# keyboard-tester.net
KiCad netlist of a schematic drawn in EAGLE
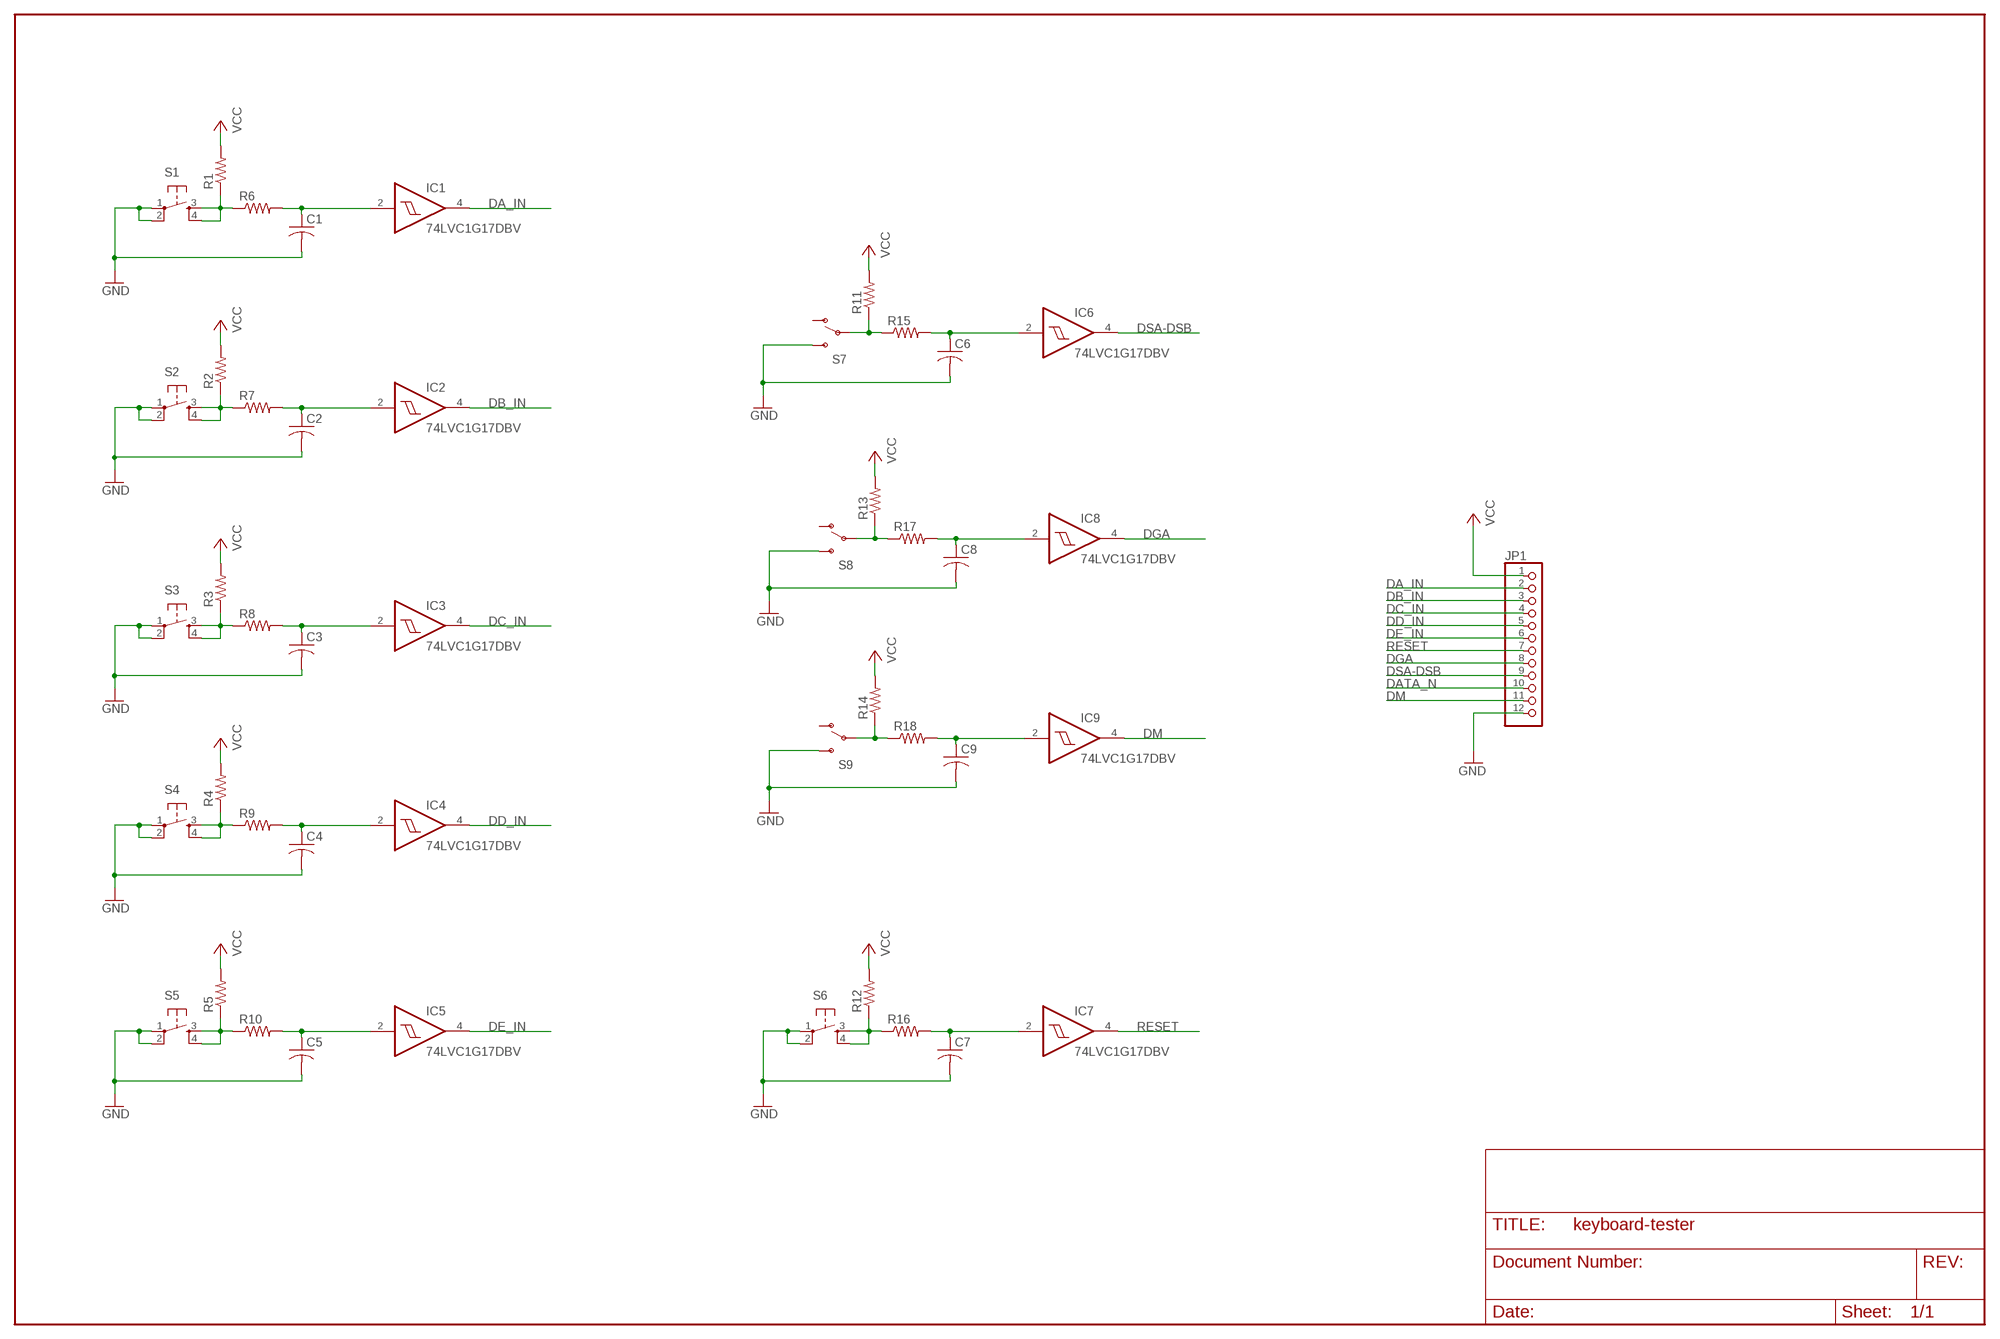
[diagram p0: schematic, sheet 1]

(export (version "E")
  (design (tool "Eeschema 10.0.6"))
  (components
    (comp (ref "C1")
      (value "C-USC0805")
      (footprint "eagle-import:C0805")
      (libsource (lib "eagle-import") (part "C-USC0805"))
    )
    (comp (ref "C2")
      (value "C-USC0805")
      (footprint "eagle-import:C0805")
      (libsource (lib "eagle-import") (part "C-USC0805"))
    )
    (comp (ref "C3")
      (value "C-USC0805")
      (footprint "eagle-import:C0805")
      (libsource (lib "eagle-import") (part "C-USC0805"))
    )
    (comp (ref "C4")
      (value "C-USC0805")
      (footprint "eagle-import:C0805")
      (libsource (lib "eagle-import") (part "C-USC0805"))
    )
    (comp (ref "C5")
      (value "C-USC0805")
      (footprint "eagle-import:C0805")
      (libsource (lib "eagle-import") (part "C-USC0805"))
    )
    (comp (ref "C6")
      (value "C-USC0805")
      (footprint "eagle-import:C0805")
      (libsource (lib "eagle-import") (part "C-USC0805"))
    )
    (comp (ref "C7")
      (value "C-USC0805")
      (footprint "eagle-import:C0805")
      (libsource (lib "eagle-import") (part "C-USC0805"))
    )
    (comp (ref "C8")
      (value "C-USC0805")
      (footprint "eagle-import:C0805")
      (libsource (lib "eagle-import") (part "C-USC0805"))
    )
    (comp (ref "C9")
      (value "C-USC0805")
      (footprint "eagle-import:C0805")
      (libsource (lib "eagle-import") (part "C-USC0805"))
    )
    (comp (ref "IC1")
      (value "74LVC1G17DBV")
      (footprint "eagle-import:SOT23-5")
      (libsource (lib "eagle-import") (part "741G17DBVLVC"))
    )
    (comp (ref "IC2")
      (value "74LVC1G17DBV")
      (footprint "eagle-import:SOT23-5")
      (libsource (lib "eagle-import") (part "741G17DBVLVC"))
    )
    (comp (ref "IC3")
      (value "74LVC1G17DBV")
      (footprint "eagle-import:SOT23-5")
      (libsource (lib "eagle-import") (part "741G17DBVLVC"))
    )
    (comp (ref "IC4")
      (value "74LVC1G17DBV")
      (footprint "eagle-import:SOT23-5")
      (libsource (lib "eagle-import") (part "741G17DBVLVC"))
    )
    (comp (ref "IC5")
      (value "74LVC1G17DBV")
      (footprint "eagle-import:SOT23-5")
      (libsource (lib "eagle-import") (part "741G17DBVLVC"))
    )
    (comp (ref "IC6")
      (value "74LVC1G17DBV")
      (footprint "eagle-import:SOT23-5")
      (libsource (lib "eagle-import") (part "741G17DBVLVC"))
    )
    (comp (ref "IC7")
      (value "74LVC1G17DBV")
      (footprint "eagle-import:SOT23-5")
      (libsource (lib "eagle-import") (part "741G17DBVLVC"))
    )
    (comp (ref "IC8")
      (value "74LVC1G17DBV")
      (footprint "eagle-import:SOT23-5")
      (libsource (lib "eagle-import") (part "741G17DBVLVC"))
    )
    (comp (ref "IC9")
      (value "74LVC1G17DBV")
      (footprint "eagle-import:SOT23-5")
      (libsource (lib "eagle-import") (part "741G17DBVLVC"))
    )
    (comp (ref "JP1")
      (value "PINHD-1X12")
      (footprint "eagle-import:1X12")
      (libsource (lib "eagle-import") (part "PINHD-1X12"))
    )
    (comp (ref "R1")
      (value "R-US_R0805")
      (footprint "eagle-import:R0805")
      (libsource (lib "eagle-import") (part "R-US_R0805"))
    )
    (comp (ref "R2")
      (value "R-US_R0805")
      (footprint "eagle-import:R0805")
      (libsource (lib "eagle-import") (part "R-US_R0805"))
    )
    (comp (ref "R3")
      (value "R-US_R0805")
      (footprint "eagle-import:R0805")
      (libsource (lib "eagle-import") (part "R-US_R0805"))
    )
    (comp (ref "R4")
      (value "R-US_R0805")
      (footprint "eagle-import:R0805")
      (libsource (lib "eagle-import") (part "R-US_R0805"))
    )
    (comp (ref "R5")
      (value "R-US_R0805")
      (footprint "eagle-import:R0805")
      (libsource (lib "eagle-import") (part "R-US_R0805"))
    )
    (comp (ref "R6")
      (value "R-US_R0805")
      (footprint "eagle-import:R0805")
      (libsource (lib "eagle-import") (part "R-US_R0805"))
    )
    (comp (ref "R7")
      (value "R-US_R0805")
      (footprint "eagle-import:R0805")
      (libsource (lib "eagle-import") (part "R-US_R0805"))
    )
    (comp (ref "R8")
      (value "R-US_R0805")
      (footprint "eagle-import:R0805")
      (libsource (lib "eagle-import") (part "R-US_R0805"))
    )
    (comp (ref "R9")
      (value "R-US_R0805")
      (footprint "eagle-import:R0805")
      (libsource (lib "eagle-import") (part "R-US_R0805"))
    )
    (comp (ref "R10")
      (value "R-US_R0805")
      (footprint "eagle-import:R0805")
      (libsource (lib "eagle-import") (part "R-US_R0805"))
    )
    (comp (ref "R11")
      (value "R-US_R0805")
      (footprint "eagle-import:R0805")
      (libsource (lib "eagle-import") (part "R-US_R0805"))
    )
    (comp (ref "R12")
      (value "R-US_R0805")
      (footprint "eagle-import:R0805")
      (libsource (lib "eagle-import") (part "R-US_R0805"))
    )
    (comp (ref "R13")
      (value "R-US_R0805")
      (footprint "eagle-import:R0805")
      (libsource (lib "eagle-import") (part "R-US_R0805"))
    )
    (comp (ref "R14")
      (value "R-US_R0805")
      (footprint "eagle-import:R0805")
      (libsource (lib "eagle-import") (part "R-US_R0805"))
    )
    (comp (ref "R15")
      (value "R-US_R0805")
      (footprint "eagle-import:R0805")
      (libsource (lib "eagle-import") (part "R-US_R0805"))
    )
    (comp (ref "R16")
      (value "R-US_R0805")
      (footprint "eagle-import:R0805")
      (libsource (lib "eagle-import") (part "R-US_R0805"))
    )
    (comp (ref "R17")
      (value "R-US_R0805")
      (footprint "eagle-import:R0805")
      (libsource (lib "eagle-import") (part "R-US_R0805"))
    )
    (comp (ref "R18")
      (value "R-US_R0805")
      (footprint "eagle-import:R0805")
      (libsource (lib "eagle-import") (part "R-US_R0805"))
    )
    (comp (ref "S1")
      (value "TAC_SWITCHPTH")
      (footprint "eagle-import:TACTILE-PTH")
      (libsource (lib "eagle-import") (part "TAC_SWITCHPTH"))
    )
    (comp (ref "S2")
      (value "TAC_SWITCHPTH")
      (footprint "eagle-import:TACTILE-PTH")
      (libsource (lib "eagle-import") (part "TAC_SWITCHPTH"))
    )
    (comp (ref "S3")
      (value "TAC_SWITCHPTH")
      (footprint "eagle-import:TACTILE-PTH")
      (libsource (lib "eagle-import") (part "TAC_SWITCHPTH"))
    )
    (comp (ref "S4")
      (value "TAC_SWITCHPTH")
      (footprint "eagle-import:TACTILE-PTH")
      (libsource (lib "eagle-import") (part "TAC_SWITCHPTH"))
    )
    (comp (ref "S5")
      (value "TAC_SWITCHPTH")
      (footprint "eagle-import:TACTILE-PTH")
      (libsource (lib "eagle-import") (part "TAC_SWITCHPTH"))
    )
    (comp (ref "S6")
      (value "TAC_SWITCHPTH")
      (footprint "eagle-import:TACTILE-PTH")
      (libsource (lib "eagle-import") (part "TAC_SWITCHPTH"))
    )
    (comp (ref "S7")
      (value "SWITCH-SPDTPTH")
      (footprint "eagle-import:SWITCH-SPDT")
      (libsource (lib "eagle-import") (part "SWITCH-SPDTPTH"))
    )
    (comp (ref "S8")
      (value "SWITCH-SPDTPTH")
      (footprint "eagle-import:SWITCH-SPDT")
      (libsource (lib "eagle-import") (part "SWITCH-SPDTPTH"))
    )
    (comp (ref "S9")
      (value "SWITCH-SPDTPTH")
      (footprint "eagle-import:SWITCH-SPDT")
      (libsource (lib "eagle-import") (part "SWITCH-SPDTPTH"))
    )
  )
  (nets
    (net (code "1") (name "/DATA_N") (class "Default")
      (node (ref "JP1") (pin "10") (pinfunction "10_10") (pintype "passive"))
    )
    (net (code "2") (name "/DA_IN") (class "Default")
      (node (ref "IC1") (pin "4") (pinfunction "O_4") (pintype "output"))
      (node (ref "JP1") (pin "2") (pinfunction "2_2") (pintype "passive"))
    )
    (net (code "3") (name "/DB_IN") (class "Default")
      (node (ref "IC2") (pin "4") (pinfunction "O_4") (pintype "output"))
      (node (ref "JP1") (pin "3") (pinfunction "3_3") (pintype "passive"))
    )
    (net (code "4") (name "/DC_IN") (class "Default")
      (node (ref "IC3") (pin "4") (pinfunction "O_4") (pintype "output"))
      (node (ref "JP1") (pin "4") (pinfunction "4_4") (pintype "passive"))
    )
    (net (code "5") (name "/DD_IN") (class "Default")
      (node (ref "IC4") (pin "4") (pinfunction "O_4") (pintype "output"))
      (node (ref "JP1") (pin "5") (pinfunction "5_5") (pintype "passive"))
    )
    (net (code "6") (name "/DE_IN") (class "Default")
      (node (ref "IC5") (pin "4") (pinfunction "O_4") (pintype "output"))
      (node (ref "JP1") (pin "6") (pinfunction "6_6") (pintype "passive"))
    )
    (net (code "7") (name "/DGA") (class "Default")
      (node (ref "IC8") (pin "4") (pinfunction "O_4") (pintype "output"))
      (node (ref "JP1") (pin "8") (pinfunction "8_8") (pintype "passive"))
    )
    (net (code "8") (name "/DM") (class "Default")
      (node (ref "IC9") (pin "4") (pinfunction "O_4") (pintype "output"))
      (node (ref "JP1") (pin "11") (pinfunction "11_11") (pintype "passive"))
    )
    (net (code "9") (name "/DSA-DSB") (class "Default")
      (node (ref "IC6") (pin "4") (pinfunction "O_4") (pintype "output"))
      (node (ref "JP1") (pin "9") (pinfunction "9_9") (pintype "passive"))
    )
    (net (code "10") (name "/RESET") (class "Default")
      (node (ref "IC7") (pin "4") (pinfunction "O_4") (pintype "output"))
      (node (ref "JP1") (pin "7") (pinfunction "7_7") (pintype "passive"))
    )
    (net (code "11") (name "GND") (class "Default")
      (node (ref "C1") (pin "2") (pinfunction "2_2") (pintype "passive"))
      (node (ref "C2") (pin "2") (pinfunction "2_2") (pintype "passive"))
      (node (ref "C3") (pin "2") (pinfunction "2_2") (pintype "passive"))
      (node (ref "C4") (pin "2") (pinfunction "2_2") (pintype "passive"))
      (node (ref "C5") (pin "2") (pinfunction "2_2") (pintype "passive"))
      (node (ref "C6") (pin "2") (pinfunction "2_2") (pintype "passive"))
      (node (ref "C7") (pin "2") (pinfunction "2_2") (pintype "passive"))
      (node (ref "C8") (pin "2") (pinfunction "2_2") (pintype "passive"))
      (node (ref "C9") (pin "2") (pinfunction "2_2") (pintype "passive"))
      (node (ref "JP1") (pin "12") (pinfunction "12_12") (pintype "passive"))
      (node (ref "S1") (pin "1") (pinfunction "1_1") (pintype "passive"))
      (node (ref "S1") (pin "2") (pinfunction "2_2") (pintype "passive"))
      (node (ref "S2") (pin "1") (pinfunction "1_1") (pintype "passive"))
      (node (ref "S2") (pin "2") (pinfunction "2_2") (pintype "passive"))
      (node (ref "S3") (pin "1") (pinfunction "1_1") (pintype "passive"))
      (node (ref "S3") (pin "2") (pinfunction "2_2") (pintype "passive"))
      (node (ref "S4") (pin "1") (pinfunction "1_1") (pintype "passive"))
      (node (ref "S4") (pin "2") (pinfunction "2_2") (pintype "passive"))
      (node (ref "S5") (pin "1") (pinfunction "1_1") (pintype "passive"))
      (node (ref "S5") (pin "2") (pinfunction "2_2") (pintype "passive"))
      (node (ref "S6") (pin "1") (pinfunction "1_1") (pintype "passive"))
      (node (ref "S6") (pin "2") (pinfunction "2_2") (pintype "passive"))
      (node (ref "S7") (pin "3") (pinfunction "S_3") (pintype "passive"))
      (node (ref "S8") (pin "3") (pinfunction "S_3") (pintype "passive"))
      (node (ref "S9") (pin "3") (pinfunction "S_3") (pintype "passive"))
    )
    (net (code "12") (name "Net-(IC1A-I)") (class "Default")
      (node (ref "C1") (pin "1") (pinfunction "1_1") (pintype "passive"))
      (node (ref "IC1") (pin "2") (pinfunction "I_2") (pintype "input"))
      (node (ref "R6") (pin "2") (pinfunction "2_2") (pintype "passive"))
    )
    (net (code "13") (name "Net-(IC2A-I)") (class "Default")
      (node (ref "C2") (pin "1") (pinfunction "1_1") (pintype "passive"))
      (node (ref "IC2") (pin "2") (pinfunction "I_2") (pintype "input"))
      (node (ref "R7") (pin "2") (pinfunction "2_2") (pintype "passive"))
    )
    (net (code "14") (name "Net-(IC3A-I)") (class "Default")
      (node (ref "C3") (pin "1") (pinfunction "1_1") (pintype "passive"))
      (node (ref "IC3") (pin "2") (pinfunction "I_2") (pintype "input"))
      (node (ref "R8") (pin "2") (pinfunction "2_2") (pintype "passive"))
    )
    (net (code "15") (name "Net-(IC4A-I)") (class "Default")
      (node (ref "C4") (pin "1") (pinfunction "1_1") (pintype "passive"))
      (node (ref "IC4") (pin "2") (pinfunction "I_2") (pintype "input"))
      (node (ref "R9") (pin "2") (pinfunction "2_2") (pintype "passive"))
    )
    (net (code "16") (name "Net-(IC5A-I)") (class "Default")
      (node (ref "C5") (pin "1") (pinfunction "1_1") (pintype "passive"))
      (node (ref "IC5") (pin "2") (pinfunction "I_2") (pintype "input"))
      (node (ref "R10") (pin "2") (pinfunction "2_2") (pintype "passive"))
    )
    (net (code "17") (name "Net-(IC6A-I)") (class "Default")
      (node (ref "C6") (pin "1") (pinfunction "1_1") (pintype "passive"))
      (node (ref "IC6") (pin "2") (pinfunction "I_2") (pintype "input"))
      (node (ref "R15") (pin "2") (pinfunction "2_2") (pintype "passive"))
    )
    (net (code "18") (name "Net-(IC7A-I)") (class "Default")
      (node (ref "C7") (pin "1") (pinfunction "1_1") (pintype "passive"))
      (node (ref "IC7") (pin "2") (pinfunction "I_2") (pintype "input"))
      (node (ref "R16") (pin "2") (pinfunction "2_2") (pintype "passive"))
    )
    (net (code "19") (name "Net-(IC8A-I)") (class "Default")
      (node (ref "C8") (pin "1") (pinfunction "1_1") (pintype "passive"))
      (node (ref "IC8") (pin "2") (pinfunction "I_2") (pintype "input"))
      (node (ref "R17") (pin "2") (pinfunction "2_2") (pintype "passive"))
    )
    (net (code "20") (name "Net-(IC9A-I)") (class "Default")
      (node (ref "C9") (pin "1") (pinfunction "1_1") (pintype "passive"))
      (node (ref "IC9") (pin "2") (pinfunction "I_2") (pintype "input"))
      (node (ref "R18") (pin "2") (pinfunction "2_2") (pintype "passive"))
    )
    (net (code "21") (name "Net-(R1-Pad1)") (class "Default")
      (node (ref "R1") (pin "1") (pinfunction "1_1") (pintype "passive"))
      (node (ref "R6") (pin "1") (pinfunction "1_1") (pintype "passive"))
      (node (ref "S1") (pin "3") (pinfunction "3_3") (pintype "passive"))
      (node (ref "S1") (pin "4") (pinfunction "4_4") (pintype "passive"))
    )
    (net (code "22") (name "Net-(R2-Pad1)") (class "Default")
      (node (ref "R2") (pin "1") (pinfunction "1_1") (pintype "passive"))
      (node (ref "R7") (pin "1") (pinfunction "1_1") (pintype "passive"))
      (node (ref "S2") (pin "3") (pinfunction "3_3") (pintype "passive"))
      (node (ref "S2") (pin "4") (pinfunction "4_4") (pintype "passive"))
    )
    (net (code "23") (name "Net-(R3-Pad1)") (class "Default")
      (node (ref "R3") (pin "1") (pinfunction "1_1") (pintype "passive"))
      (node (ref "R8") (pin "1") (pinfunction "1_1") (pintype "passive"))
      (node (ref "S3") (pin "3") (pinfunction "3_3") (pintype "passive"))
      (node (ref "S3") (pin "4") (pinfunction "4_4") (pintype "passive"))
    )
    (net (code "24") (name "Net-(R4-Pad1)") (class "Default")
      (node (ref "R4") (pin "1") (pinfunction "1_1") (pintype "passive"))
      (node (ref "R9") (pin "1") (pinfunction "1_1") (pintype "passive"))
      (node (ref "S4") (pin "3") (pinfunction "3_3") (pintype "passive"))
      (node (ref "S4") (pin "4") (pinfunction "4_4") (pintype "passive"))
    )
    (net (code "25") (name "Net-(R10-Pad1)") (class "Default")
      (node (ref "R10") (pin "1") (pinfunction "1_1") (pintype "passive"))
      (node (ref "R5") (pin "1") (pinfunction "1_1") (pintype "passive"))
      (node (ref "S5") (pin "3") (pinfunction "3_3") (pintype "passive"))
      (node (ref "S5") (pin "4") (pinfunction "4_4") (pintype "passive"))
    )
    (net (code "26") (name "Net-(R12-Pad1)") (class "Default")
      (node (ref "R12") (pin "1") (pinfunction "1_1") (pintype "passive"))
      (node (ref "R16") (pin "1") (pinfunction "1_1") (pintype "passive"))
      (node (ref "S6") (pin "3") (pinfunction "3_3") (pintype "passive"))
      (node (ref "S6") (pin "4") (pinfunction "4_4") (pintype "passive"))
    )
    (net (code "27") (name "Net-(S7-P)") (class "Default")
      (node (ref "R11") (pin "1") (pinfunction "1_1") (pintype "passive"))
      (node (ref "R15") (pin "1") (pinfunction "1_1") (pintype "passive"))
      (node (ref "S7") (pin "2") (pinfunction "P_2") (pintype "passive"))
    )
    (net (code "28") (name "Net-(S8-P)") (class "Default")
      (node (ref "R13") (pin "1") (pinfunction "1_1") (pintype "passive"))
      (node (ref "R17") (pin "1") (pinfunction "1_1") (pintype "passive"))
      (node (ref "S8") (pin "2") (pinfunction "P_2") (pintype "passive"))
    )
    (net (code "29") (name "Net-(S9-P)") (class "Default")
      (node (ref "R14") (pin "1") (pinfunction "1_1") (pintype "passive"))
      (node (ref "R18") (pin "1") (pinfunction "1_1") (pintype "passive"))
      (node (ref "S9") (pin "2") (pinfunction "P_2") (pintype "passive"))
    )
    (net (code "30") (name "VCC") (class "Default")
      (node (ref "JP1") (pin "1") (pinfunction "1_1") (pintype "passive"))
      (node (ref "R1") (pin "2") (pinfunction "2_2") (pintype "passive"))
      (node (ref "R11") (pin "2") (pinfunction "2_2") (pintype "passive"))
      (node (ref "R12") (pin "2") (pinfunction "2_2") (pintype "passive"))
      (node (ref "R13") (pin "2") (pinfunction "2_2") (pintype "passive"))
      (node (ref "R14") (pin "2") (pinfunction "2_2") (pintype "passive"))
      (node (ref "R2") (pin "2") (pinfunction "2_2") (pintype "passive"))
      (node (ref "R3") (pin "2") (pinfunction "2_2") (pintype "passive"))
      (node (ref "R4") (pin "2") (pinfunction "2_2") (pintype "passive"))
      (node (ref "R5") (pin "2") (pinfunction "2_2") (pintype "passive"))
    )
    (net (code "31") (name "unconnected-(S7-O-Pad1)") (class "Default")
      (node (ref "S7") (pin "1") (pinfunction "O_1") (pintype "passive"))
    )
    (net (code "32") (name "unconnected-(S8-O-Pad1)") (class "Default")
      (node (ref "S8") (pin "1") (pinfunction "O_1") (pintype "passive"))
    )
    (net (code "33") (name "unconnected-(S9-O-Pad1)") (class "Default")
      (node (ref "S9") (pin "1") (pinfunction "O_1") (pintype "passive"))
    )
  )
)
